# Nano_XBee.net
KiCad netlist of a schematic drawn in EAGLE
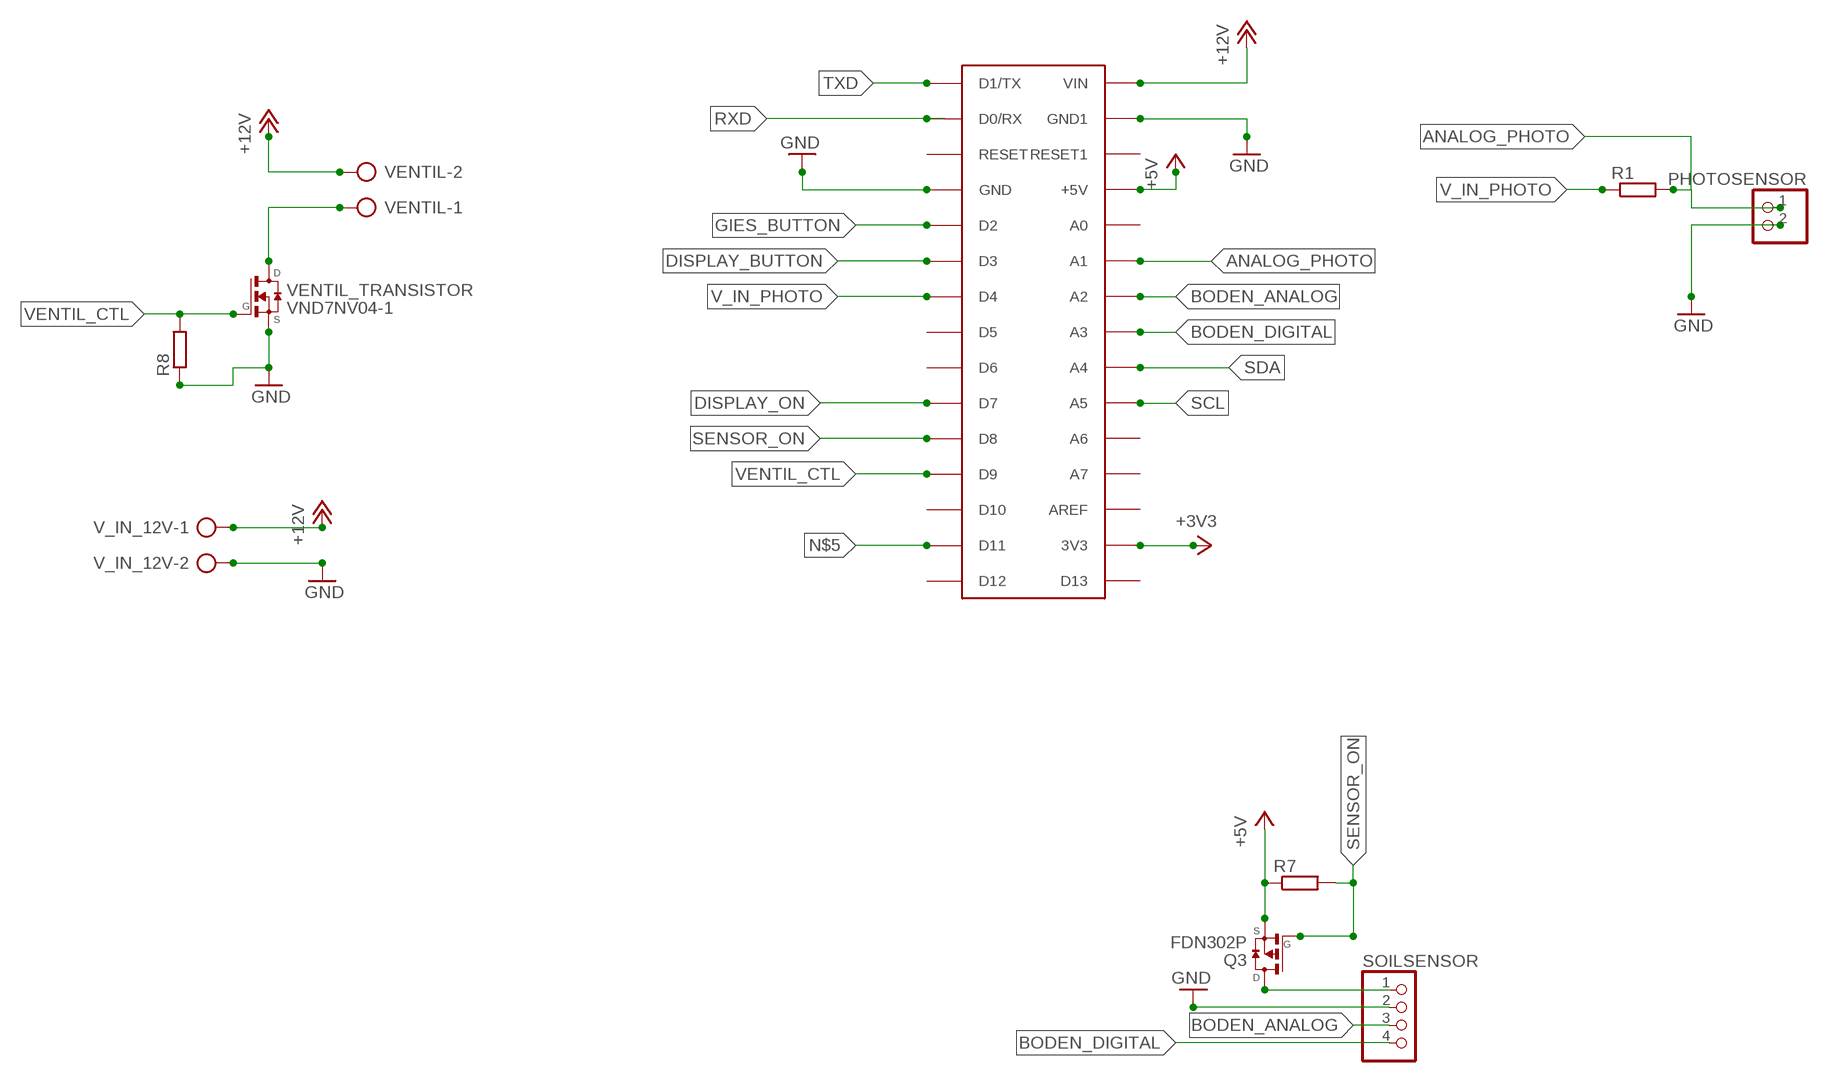
[diagram p0: schematic, sheet 1]

(export (version "E")
  (design (tool "Eeschema 10.0.6"))
  (components
    (comp (ref "PHOTOSENSOR")
      (value "PINHD-1X2")
      (footprint "eagle-import:1X02")
      (libsource (lib "eagle-import") (part "PINHD-1X2"))
    )
    (comp (ref "Q3")
      (value "FDN302P")
      (footprint "eagle-import:SSOT-3")
      (libsource (lib "eagle-import") (part "FDN302P"))
    )
    (comp (ref "R1")
      (value "R-EU_0207/7")
      (footprint "eagle-import:0207_7")
      (libsource (lib "eagle-import") (part "R-EU_0207/7"))
    )
    (comp (ref "R7")
      (value "R-EU_M0805")
      (footprint "eagle-import:M0805")
      (libsource (lib "eagle-import") (part "R-EU_M0805"))
    )
    (comp (ref "R8")
      (value "R-EU_M0805")
      (footprint "eagle-import:M0805")
      (libsource (lib "eagle-import") (part "R-EU_M0805"))
    )
    (comp (ref "SOILSENSOR")
      (value "PINHD-1X4")
      (footprint "eagle-import:1X04")
      (libsource (lib "eagle-import") (part "PINHD-1X4"))
    )
    (comp (ref "U$1")
      (value "ARDUINONANO")
      (footprint "eagle-import:PDIP-32")
      (libsource (lib "eagle-import") (part "ARDUINONANO"))
    )
    (comp (ref "VENTIL")
      (value "AK500/2")
      (footprint "eagle-import:AK500_2")
      (libsource (lib "eagle-import") (part "AK500/2"))
    )
    (comp (ref "VENTIL_TRANSISTOR")
      (value "VND7NV04-1")
      (footprint "eagle-import:IPAK")
      (libsource (lib "eagle-import") (part "VND7NV04-1"))
    )
    (comp (ref "V_IN_12V")
      (value "AK500/2")
      (footprint "eagle-import:AK500_2")
      (libsource (lib "eagle-import") (part "AK500/2"))
    )
  )
  (nets
    (net (code "1") (name "+3V3") (class "Default")
      (node (ref "U$1") (pin "3V3") (pinfunction "3V3_3V3") (pintype "bidirectional"))
    )
    (net (code "2") (name "+5V") (class "Default")
      (node (ref "Q3") (pin "2") (pinfunction "S_2") (pintype "passive"))
      (node (ref "R7") (pin "1") (pinfunction "1_1") (pintype "passive"))
      (node (ref "U$1") (pin "+5V") (pinfunction "+5V_+5V") (pintype "bidirectional"))
    )
    (net (code "3") (name "+12V") (class "Default")
      (node (ref "U$1") (pin "VIN") (pinfunction "VIN_VIN") (pintype "bidirectional"))
      (node (ref "VENTIL") (pin "2") (pinfunction "KL_2") (pintype "passive"))
      (node (ref "V_IN_12V") (pin "1") (pinfunction "KL_1") (pintype "passive"))
    )
    (net (code "4") (name "ANALOG_PHOTO") (class "Default")
      (node (ref "PHOTOSENSOR") (pin "1") (pinfunction "1_1") (pintype "passive"))
      (node (ref "R1") (pin "2") (pinfunction "2_2") (pintype "passive"))
      (node (ref "U$1") (pin "A1") (pinfunction "A1_A1") (pintype "bidirectional"))
    )
    (net (code "5") (name "BODEN_ANALOG") (class "Default")
      (node (ref "SOILSENSOR") (pin "3") (pinfunction "3_3") (pintype "passive"))
      (node (ref "U$1") (pin "A2") (pinfunction "A2_A2") (pintype "bidirectional"))
    )
    (net (code "6") (name "BODEN_DIGITAL") (class "Default")
      (node (ref "SOILSENSOR") (pin "4") (pinfunction "4_4") (pintype "passive"))
      (node (ref "U$1") (pin "A3") (pinfunction "A3_A3") (pintype "bidirectional"))
    )
    (net (code "7") (name "DISPLAY_BUTTON") (class "Default")
      (node (ref "U$1") (pin "D3") (pinfunction "D3_D3") (pintype "bidirectional"))
    )
    (net (code "8") (name "DISPLAY_ON") (class "Default")
      (node (ref "U$1") (pin "D7") (pinfunction "D7_D7") (pintype "bidirectional"))
    )
    (net (code "9") (name "GIES_BUTTON") (class "Default")
      (node (ref "U$1") (pin "D2") (pinfunction "D2_D2") (pintype "bidirectional"))
    )
    (net (code "10") (name "GND") (class "Default")
      (node (ref "PHOTOSENSOR") (pin "2") (pinfunction "2_2") (pintype "passive"))
      (node (ref "R8") (pin "1") (pinfunction "1_1") (pintype "passive"))
      (node (ref "SOILSENSOR") (pin "2") (pinfunction "2_2") (pintype "passive"))
      (node (ref "U$1") (pin "GND") (pinfunction "GND_GND") (pintype "bidirectional"))
      (node (ref "U$1") (pin "GND1") (pinfunction "GND1_GND1") (pintype "bidirectional"))
      (node (ref "VENTIL_TRANSISTOR") (pin "3") (pinfunction "S_3") (pintype "passive"))
      (node (ref "V_IN_12V") (pin "2") (pinfunction "KL_2") (pintype "passive"))
    )
    (net (code "11") (name "N$5") (class "Default")
      (node (ref "U$1") (pin "D11") (pinfunction "D11_D11") (pintype "bidirectional"))
    )
    (net (code "12") (name "Net-(Q3-D)") (class "Default")
      (node (ref "Q3") (pin "3") (pinfunction "D_3") (pintype "passive"))
      (node (ref "SOILSENSOR") (pin "1") (pinfunction "1_1") (pintype "passive"))
    )
    (net (code "13") (name "Net-(VENTILA-KL)") (class "Default")
      (node (ref "VENTIL") (pin "1") (pinfunction "KL_1") (pintype "passive"))
      (node (ref "VENTIL_TRANSISTOR") (pin "2") (pinfunction "D_2") (pintype "passive"))
    )
    (net (code "14") (name "RXD") (class "Default")
      (node (ref "U$1") (pin "D0/RX") (pinfunction "D0/RX_D0/RX") (pintype "bidirectional"))
    )
    (net (code "15") (name "SCL") (class "Default")
      (node (ref "U$1") (pin "A5") (pinfunction "A5_A5") (pintype "bidirectional"))
    )
    (net (code "16") (name "SDA") (class "Default")
      (node (ref "U$1") (pin "A4") (pinfunction "A4_A4") (pintype "bidirectional"))
    )
    (net (code "17") (name "SENSOR_ON") (class "Default")
      (node (ref "Q3") (pin "1") (pinfunction "G_1") (pintype "passive"))
      (node (ref "R7") (pin "2") (pinfunction "2_2") (pintype "passive"))
      (node (ref "U$1") (pin "D8") (pinfunction "D8_D8") (pintype "bidirectional"))
    )
    (net (code "18") (name "TXD") (class "Default")
      (node (ref "U$1") (pin "D1/TX") (pinfunction "D1/TX_D1/TX") (pintype "bidirectional"))
    )
    (net (code "19") (name "VENTIL_CTL") (class "Default")
      (node (ref "R8") (pin "2") (pinfunction "2_2") (pintype "passive"))
      (node (ref "U$1") (pin "D9") (pinfunction "D9_D9") (pintype "bidirectional"))
      (node (ref "VENTIL_TRANSISTOR") (pin "1") (pinfunction "G_1") (pintype "passive"))
    )
    (net (code "20") (name "V_IN_PHOTO") (class "Default")
      (node (ref "R1") (pin "1") (pinfunction "1_1") (pintype "passive"))
      (node (ref "U$1") (pin "D4") (pinfunction "D4_D4") (pintype "bidirectional"))
    )
    (net (code "21") (name "unconnected-(U$1-PadA0)") (class "Default")
      (node (ref "U$1") (pin "A0") (pinfunction "A0_A0") (pintype "bidirectional"))
    )
    (net (code "22") (name "unconnected-(U$1-PadA6)") (class "Default")
      (node (ref "U$1") (pin "A6") (pinfunction "A6_A6") (pintype "bidirectional"))
    )
    (net (code "23") (name "unconnected-(U$1-PadA7)") (class "Default")
      (node (ref "U$1") (pin "A7") (pinfunction "A7_A7") (pintype "bidirectional"))
    )
    (net (code "24") (name "unconnected-(U$1-PadAREF)") (class "Default")
      (node (ref "U$1") (pin "AREF") (pinfunction "AREF_AREF") (pintype "bidirectional"))
    )
    (net (code "25") (name "unconnected-(U$1-PadD5)") (class "Default")
      (node (ref "U$1") (pin "D5") (pinfunction "D5_D5") (pintype "bidirectional"))
    )
    (net (code "26") (name "unconnected-(U$1-PadD6)") (class "Default")
      (node (ref "U$1") (pin "D6") (pinfunction "D6_D6") (pintype "bidirectional"))
    )
    (net (code "27") (name "unconnected-(U$1-PadD10)") (class "Default")
      (node (ref "U$1") (pin "D10") (pinfunction "D10_D10") (pintype "bidirectional"))
    )
    (net (code "28") (name "unconnected-(U$1-PadD12)") (class "Default")
      (node (ref "U$1") (pin "D12") (pinfunction "D12_D12") (pintype "bidirectional"))
    )
    (net (code "29") (name "unconnected-(U$1-PadD13)") (class "Default")
      (node (ref "U$1") (pin "D13") (pinfunction "D13_D13") (pintype "bidirectional"))
    )
    (net (code "30") (name "unconnected-(U$1-PadRESET)") (class "Default")
      (node (ref "U$1") (pin "RESET") (pinfunction "RESET_RESET") (pintype "bidirectional"))
    )
    (net (code "31") (name "unconnected-(U$1-PadRESET1)") (class "Default")
      (node (ref "U$1") (pin "RESET1") (pinfunction "RESET1_RESET1") (pintype "bidirectional"))
    )
  )
)
